# 02_-_LcdGraphic128x64.net
KiCad netlist of a schematic drawn in Altium Designer
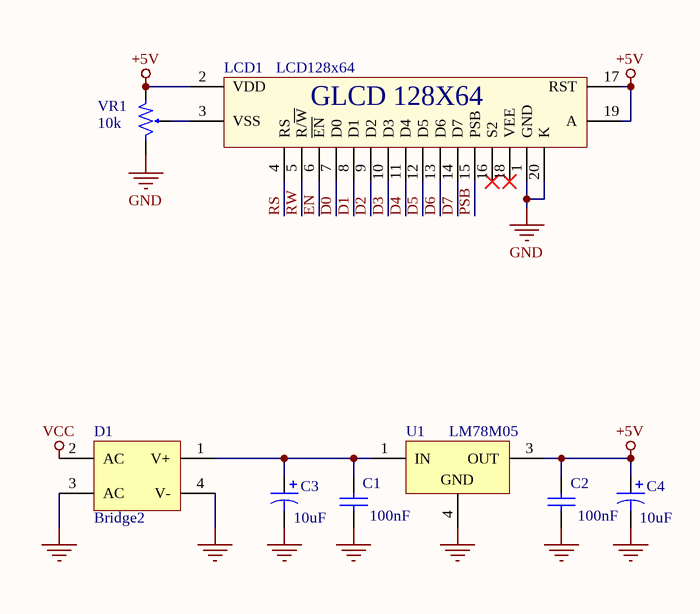
[diagram p0: 02 - LcdGraphic128x64.SchDoc]

(export (version "E")
  (design (tool "Eeschema 10.0.6"))
  (components
    (comp (ref "C1")
      (value "100nF")
      (footprint "RAD-0.3")
      (description "Capacitor")
      (fields (field (name "Comment") "104") (field (name "PUBLISHER") "Altium Limited"))
      (libsource (lib "Miscellaneous Devices") (part "Cap"))
    )
    (comp (ref "C2")
      (value "100nF")
      (footprint "RAD-0.3")
      (description "Capacitor")
      (fields (field (name "Comment") "104") (field (name "PUBLISHER") "Altium Limited"))
      (libsource (lib "Miscellaneous Devices") (part "Cap"))
    )
    (comp (ref "C3")
      (value "10uF")
      (footprint "RB7.6-15")
      (description "Polarized Capacitor (Radial)")
      (fields (field (name "Comment") "10uF/16V") (field (name "PUBLISHER") "Altium Limited"))
      (libsource (lib "Miscellaneous Devices") (part "Cap Pol1"))
    )
    (comp (ref "C4")
      (value "10uF")
      (footprint "RB7.6-15")
      (description "Polarized Capacitor (Radial)")
      (fields (field (name "Comment") "10uF/16V") (field (name "PUBLISHER") "Altium Limited"))
      (libsource (lib "Miscellaneous Devices") (part "Cap Pol1"))
    )
    (comp (ref "D1")
      (value "Bridge2")
      (footprint "D-46_6A")
      (description "Diode Bridge")
      (fields (field (name "PUBLISHER") "Altium Limited"))
      (libsource (lib "Miscellaneous Devices") (part "Bridge2"))
    )
    (comp (ref "LCD1")
      (value "LCD128x64")
      (footprint "LCD128x64")
      (description "LCD Graphic 128x64")
      (libsource (lib "LIBRARY") (part "LCD128x64"))
    )
    (comp (ref "U1")
      (value "LM78M05")
      (footprint "NDP0003B_M")
      (description "3-Terminal Positive Voltage Regulators, 3-pin TO-252")
      (fields (field (name "MANUFACTURER") "Texas Instruments") (field (name "Comment") "LM78M05CDTX"))
      (libsource (lib "Altium Content Vault") (part "CMP-0062-00204-3"))
    )
    (comp (ref "VR1")
      (value "10k")
      (footprint "VR1")
      (description "Var Resistor")
      (libsource (lib "PART") (part "VR1"))
    )
  )
  (nets
    (net (code "1") (name "+5V") (class "Default")
      (node (ref "C2") (pin "1") (pinfunction "1_1") (pintype "passive"))
      (node (ref "C4") (pin "1") (pinfunction "1_1") (pintype "passive"))
      (node (ref "LCD1") (pin "17") (pinfunction "RST_17") (pintype "passive"))
      (node (ref "LCD1") (pin "19") (pinfunction "A_19") (pintype "passive"))
      (node (ref "LCD1") (pin "2") (pinfunction "VDD_2") (pintype "passive"))
      (node (ref "U1") (pin "3") (pinfunction "OUT_3") (pintype "power_in"))
      (node (ref "VR1") (pin "1") (pinfunction "1_1") (pintype "passive"))
    )
    (net (code "2") (name "/D0") (class "Default")
      (node (ref "LCD1") (pin "7") (pinfunction "D0_7") (pintype "passive"))
    )
    (net (code "3") (name "/D1") (class "Default")
      (node (ref "LCD1") (pin "8") (pinfunction "D1_8") (pintype "passive"))
    )
    (net (code "4") (name "/D2") (class "Default")
      (node (ref "LCD1") (pin "9") (pinfunction "D2_9") (pintype "passive"))
    )
    (net (code "5") (name "/D3") (class "Default")
      (node (ref "LCD1") (pin "10") (pinfunction "D3_10") (pintype "passive"))
    )
    (net (code "6") (name "/D4") (class "Default")
      (node (ref "LCD1") (pin "11") (pinfunction "D4_11") (pintype "passive"))
    )
    (net (code "7") (name "/D5") (class "Default")
      (node (ref "LCD1") (pin "12") (pinfunction "D5_12") (pintype "passive"))
    )
    (net (code "8") (name "/D6") (class "Default")
      (node (ref "LCD1") (pin "13") (pinfunction "D6_13") (pintype "passive"))
    )
    (net (code "9") (name "/D7") (class "Default")
      (node (ref "LCD1") (pin "14") (pinfunction "D7_14") (pintype "passive"))
    )
    (net (code "10") (name "/EN") (class "Default")
      (node (ref "LCD1") (pin "6") (pinfunction "~{EN}_6") (pintype "passive"))
    )
    (net (code "11") (name "/PSB") (class "Default")
      (node (ref "LCD1") (pin "15") (pinfunction "PSB_15") (pintype "passive"))
    )
    (net (code "12") (name "/RS") (class "Default")
      (node (ref "LCD1") (pin "4") (pinfunction "RS_4") (pintype "passive"))
    )
    (net (code "13") (name "/RW") (class "Default")
      (node (ref "LCD1") (pin "5") (pinfunction "R/~{W}_5") (pintype "passive"))
    )
    (net (code "14") (name "GND") (class "Default")
      (node (ref "C1") (pin "2") (pinfunction "2_2") (pintype "passive"))
      (node (ref "C2") (pin "2") (pinfunction "2_2") (pintype "passive"))
      (node (ref "C3") (pin "2") (pinfunction "2_2") (pintype "passive"))
      (node (ref "C4") (pin "2") (pinfunction "2_2") (pintype "passive"))
      (node (ref "D1") (pin "3") (pinfunction "AC_3") (pintype "passive"))
      (node (ref "D1") (pin "4") (pinfunction "V-_4") (pintype "passive"))
      (node (ref "LCD1") (pin "1") (pinfunction "GND_1") (pintype "passive"))
      (node (ref "LCD1") (pin "20") (pinfunction "K_20") (pintype "passive"))
      (node (ref "U1") (pin "4") (pinfunction "GND_4") (pintype "power_in"))
      (node (ref "VR1") (pin "3") (pinfunction "3_3") (pintype "passive"))
    )
    (net (code "15") (name "Net-(D1-V+)") (class "Default")
      (node (ref "C1") (pin "1") (pinfunction "1_1") (pintype "passive"))
      (node (ref "C3") (pin "1") (pinfunction "1_1") (pintype "passive"))
      (node (ref "D1") (pin "1") (pinfunction "V+_1") (pintype "passive"))
      (node (ref "U1") (pin "1") (pinfunction "IN_1") (pintype "power_in"))
    )
    (net (code "16") (name "Net-(LCD1-VSS)") (class "Default")
      (node (ref "LCD1") (pin "3") (pinfunction "VSS_3") (pintype "passive"))
      (node (ref "VR1") (pin "2") (pinfunction "2_2") (pintype "passive"))
    )
    (net (code "17") (name "VCC") (class "Default")
      (node (ref "D1") (pin "2") (pinfunction "AC_2") (pintype "passive"))
    )
    (net (code "18") (name "unconnected-(LCD1-S2-Pad16)") (class "Default")
      (node (ref "LCD1") (pin "16") (pinfunction "S2_16") (pintype "passive+no_connect"))
    )
    (net (code "19") (name "unconnected-(LCD1-VEE-Pad18)") (class "Default")
      (node (ref "LCD1") (pin "18") (pinfunction "VEE_18") (pintype "passive+no_connect"))
    )
  )
)
